# hw4-schematic.net
KiCad netlist of a schematic drawn in EAGLE
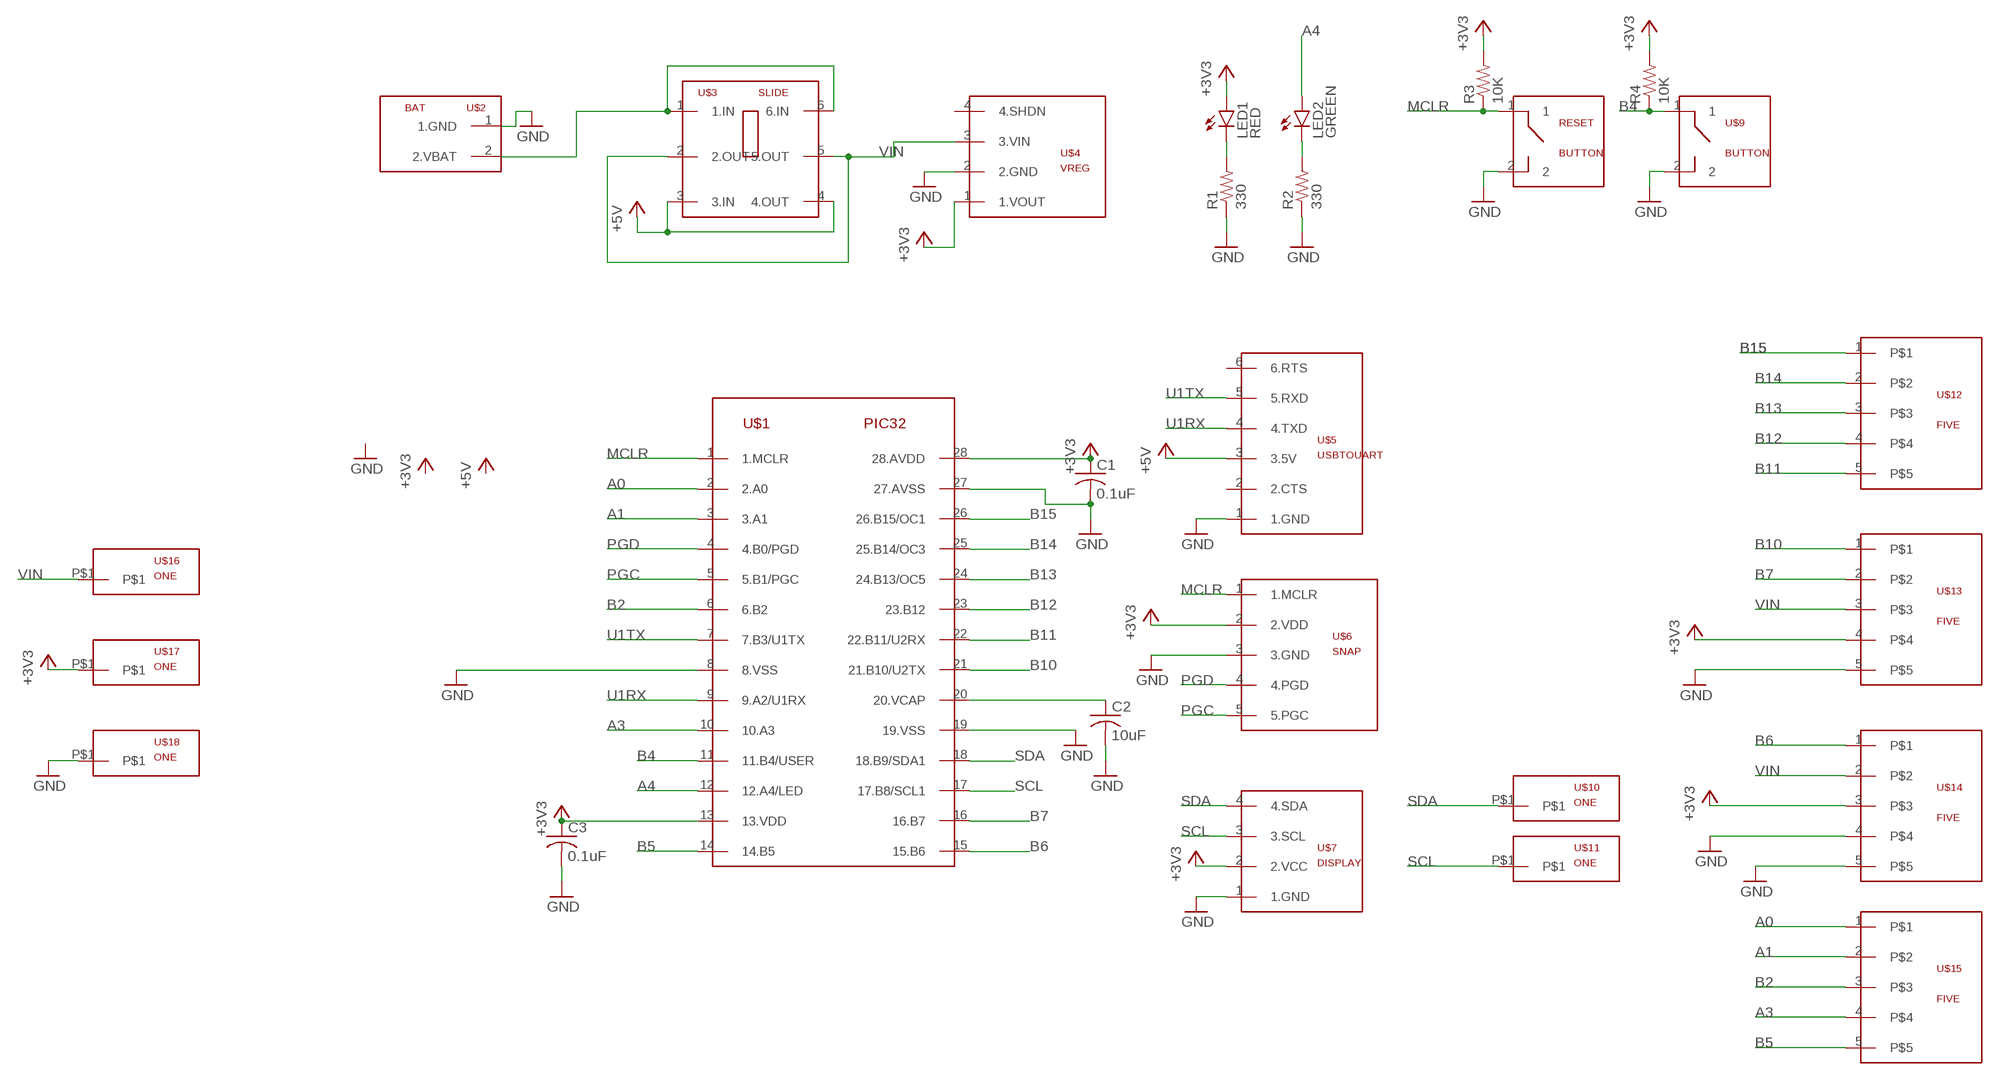
[diagram p0: schematic, sheet 1]

(export (version "E")
  (design (tool "Eeschema 10.0.6"))
  (components
    (comp (ref "C1")
      (value "0.1uF")
      (footprint "eagle-import:C025-024X044")
      (libsource (lib "eagle-import") (part "C-US025-024X044"))
    )
    (comp (ref "C2")
      (value "10uF")
      (footprint "eagle-import:C025-024X044")
      (libsource (lib "eagle-import") (part "C-US025-024X044"))
    )
    (comp (ref "C3")
      (value "0.1uF")
      (footprint "eagle-import:C025-024X044")
      (libsource (lib "eagle-import") (part "C-US025-024X044"))
    )
    (comp (ref "LED1")
      (value "RED")
      (footprint "eagle-import:LED3MM")
      (libsource (lib "eagle-import") (part "LED3MM"))
    )
    (comp (ref "LED2")
      (value "GREEN")
      (footprint "eagle-import:LED3MM")
      (libsource (lib "eagle-import") (part "LED3MM"))
    )
    (comp (ref "R1")
      (value "330")
      (footprint "eagle-import:0207_7")
      (libsource (lib "eagle-import") (part "R-US_0207/7"))
    )
    (comp (ref "R2")
      (value "330")
      (footprint "eagle-import:0207_7")
      (libsource (lib "eagle-import") (part "R-US_0207/7"))
    )
    (comp (ref "R3")
      (value "10K")
      (footprint "eagle-import:0207_7")
      (libsource (lib "eagle-import") (part "R-US_0207/7"))
    )
    (comp (ref "R4")
      (value "10K")
      (footprint "eagle-import:0207_7")
      (libsource (lib "eagle-import") (part "R-US_0207/7"))
    )
    (comp (ref "RESET")
      (value "BUTTON")
      (footprint "eagle-import:BUTTON")
      (libsource (lib "eagle-import") (part "BUTTON"))
    )
    (comp (ref "U$1")
      (value "PIC32")
      (footprint "eagle-import:DIL28-3")
      (libsource (lib "eagle-import") (part "PIC32"))
    )
    (comp (ref "U$2")
      (value "BAT")
      (footprint "eagle-import:BAT")
      (libsource (lib "eagle-import") (part "BAT"))
    )
    (comp (ref "U$3")
      (value "SLIDE")
      (footprint "eagle-import:SLIDE")
      (libsource (lib "eagle-import") (part "SLIDE"))
    )
    (comp (ref "U$4")
      (value "VREG")
      (footprint "eagle-import:VREG")
      (libsource (lib "eagle-import") (part "VREG"))
    )
    (comp (ref "U$5")
      (value "USBTOUART")
      (footprint "eagle-import:USBTOUART")
      (libsource (lib "eagle-import") (part "USBTOUART"))
    )
    (comp (ref "U$6")
      (value "SNAP")
      (footprint "eagle-import:SNAP")
      (libsource (lib "eagle-import") (part "SNAP"))
    )
    (comp (ref "U$7")
      (value "DISPLAY")
      (footprint "eagle-import:DISPLAY")
      (libsource (lib "eagle-import") (part "DISPLAY"))
    )
    (comp (ref "U$9")
      (value "BUTTON")
      (footprint "eagle-import:BUTTON")
      (libsource (lib "eagle-import") (part "BUTTON"))
    )
    (comp (ref "U$10")
      (value "ONE")
      (footprint "eagle-import:ONE")
      (libsource (lib "eagle-import") (part "ONE"))
    )
    (comp (ref "U$11")
      (value "ONE")
      (footprint "eagle-import:ONE")
      (libsource (lib "eagle-import") (part "ONE"))
    )
    (comp (ref "U$12")
      (value "FIVE")
      (footprint "eagle-import:FIVE")
      (libsource (lib "eagle-import") (part "FIVE"))
    )
    (comp (ref "U$13")
      (value "FIVE")
      (footprint "eagle-import:FIVE")
      (libsource (lib "eagle-import") (part "FIVE"))
    )
    (comp (ref "U$14")
      (value "FIVE")
      (footprint "eagle-import:FIVE")
      (libsource (lib "eagle-import") (part "FIVE"))
    )
    (comp (ref "U$15")
      (value "FIVE")
      (footprint "eagle-import:FIVE")
      (libsource (lib "eagle-import") (part "FIVE"))
    )
    (comp (ref "U$16")
      (value "ONE")
      (footprint "eagle-import:ONE")
      (libsource (lib "eagle-import") (part "ONE"))
    )
    (comp (ref "U$17")
      (value "ONE")
      (footprint "eagle-import:ONE")
      (libsource (lib "eagle-import") (part "ONE"))
    )
    (comp (ref "U$18")
      (value "ONE")
      (footprint "eagle-import:ONE")
      (libsource (lib "eagle-import") (part "ONE"))
    )
  )
  (nets
    (net (code "1") (name "+3V3") (class "Default")
      (node (ref "C1") (pin "1") (pinfunction "1_1") (pintype "passive"))
      (node (ref "C3") (pin "1") (pinfunction "1_1") (pintype "passive"))
      (node (ref "LED1") (pin "A") (pinfunction "A_A") (pintype "passive"))
      (node (ref "R3") (pin "2") (pinfunction "2_2") (pintype "passive"))
      (node (ref "R4") (pin "2") (pinfunction "2_2") (pintype "passive"))
      (node (ref "U$1") (pin "13") (pinfunction "13.VDD_13") (pintype "bidirectional"))
      (node (ref "U$1") (pin "28") (pinfunction "28.AVDD_28") (pintype "bidirectional"))
      (node (ref "U$13") (pin "4") (pinfunction "P$4_4") (pintype "bidirectional"))
      (node (ref "U$14") (pin "3") (pinfunction "P$3_3") (pintype "bidirectional"))
      (node (ref "U$17") (pin "P$1") (pinfunction "P$1_P$1") (pintype "bidirectional"))
      (node (ref "U$4") (pin "1") (pinfunction "1.VOUT_1") (pintype "bidirectional"))
      (node (ref "U$6") (pin "2") (pinfunction "2.VDD_2") (pintype "bidirectional"))
      (node (ref "U$7") (pin "2") (pinfunction "2.VCC_2") (pintype "bidirectional"))
    )
    (net (code "2") (name "+5V") (class "Default")
      (node (ref "U$3") (pin "3") (pinfunction "3.IN_3") (pintype "bidirectional"))
      (node (ref "U$3") (pin "4") (pinfunction "4.OUT_4") (pintype "bidirectional"))
      (node (ref "U$5") (pin "3") (pinfunction "3.5V_3") (pintype "bidirectional"))
    )
    (net (code "3") (name "/A0") (class "Default")
      (node (ref "U$1") (pin "2") (pinfunction "2.A0_2") (pintype "bidirectional"))
      (node (ref "U$15") (pin "1") (pinfunction "P$1_1") (pintype "bidirectional"))
    )
    (net (code "4") (name "/A1") (class "Default")
      (node (ref "U$1") (pin "3") (pinfunction "3.A1_3") (pintype "bidirectional"))
      (node (ref "U$15") (pin "2") (pinfunction "P$2_2") (pintype "bidirectional"))
    )
    (net (code "5") (name "/A3") (class "Default")
      (node (ref "U$1") (pin "10") (pinfunction "10.A3_10") (pintype "bidirectional"))
      (node (ref "U$15") (pin "4") (pinfunction "P$4_4") (pintype "bidirectional"))
    )
    (net (code "6") (name "/A4") (class "Default")
      (node (ref "LED2") (pin "A") (pinfunction "A_A") (pintype "passive"))
      (node (ref "U$1") (pin "12") (pinfunction "12.A4/LED_12") (pintype "bidirectional"))
    )
    (net (code "7") (name "/B2") (class "Default")
      (node (ref "U$1") (pin "6") (pinfunction "6.B2_6") (pintype "bidirectional"))
      (node (ref "U$15") (pin "3") (pinfunction "P$3_3") (pintype "bidirectional"))
    )
    (net (code "8") (name "/B4") (class "Default")
      (node (ref "R4") (pin "1") (pinfunction "1_1") (pintype "passive"))
      (node (ref "U$1") (pin "11") (pinfunction "11.B4/USER_11") (pintype "bidirectional"))
      (node (ref "U$9") (pin "1") (pinfunction "1_1") (pintype "bidirectional"))
    )
    (net (code "9") (name "/B5") (class "Default")
      (node (ref "U$1") (pin "14") (pinfunction "14.B5_14") (pintype "bidirectional"))
      (node (ref "U$15") (pin "5") (pinfunction "P$5_5") (pintype "bidirectional"))
    )
    (net (code "10") (name "/B6") (class "Default")
      (node (ref "U$1") (pin "15") (pinfunction "15.B6_15") (pintype "bidirectional"))
      (node (ref "U$14") (pin "1") (pinfunction "P$1_1") (pintype "bidirectional"))
    )
    (net (code "11") (name "/B7") (class "Default")
      (node (ref "U$1") (pin "16") (pinfunction "16.B7_16") (pintype "bidirectional"))
      (node (ref "U$13") (pin "2") (pinfunction "P$2_2") (pintype "bidirectional"))
    )
    (net (code "12") (name "/B10") (class "Default")
      (node (ref "U$1") (pin "21") (pinfunction "21.B10/U2TX_21") (pintype "bidirectional"))
      (node (ref "U$13") (pin "1") (pinfunction "P$1_1") (pintype "bidirectional"))
    )
    (net (code "13") (name "/B11") (class "Default")
      (node (ref "U$1") (pin "22") (pinfunction "22.B11/U2RX_22") (pintype "bidirectional"))
      (node (ref "U$12") (pin "5") (pinfunction "P$5_5") (pintype "bidirectional"))
    )
    (net (code "14") (name "/B12") (class "Default")
      (node (ref "U$1") (pin "23") (pinfunction "23.B12_23") (pintype "bidirectional"))
      (node (ref "U$12") (pin "4") (pinfunction "P$4_4") (pintype "bidirectional"))
    )
    (net (code "15") (name "/B13") (class "Default")
      (node (ref "U$1") (pin "24") (pinfunction "24.B13/OC5_24") (pintype "bidirectional"))
      (node (ref "U$12") (pin "3") (pinfunction "P$3_3") (pintype "bidirectional"))
    )
    (net (code "16") (name "/B14") (class "Default")
      (node (ref "U$1") (pin "25") (pinfunction "25.B14/OC3_25") (pintype "bidirectional"))
      (node (ref "U$12") (pin "2") (pinfunction "P$2_2") (pintype "bidirectional"))
    )
    (net (code "17") (name "/B15") (class "Default")
      (node (ref "U$1") (pin "26") (pinfunction "26.B15/OC1_26") (pintype "bidirectional"))
      (node (ref "U$12") (pin "1") (pinfunction "P$1_1") (pintype "bidirectional"))
    )
    (net (code "18") (name "/MCLR") (class "Default")
      (node (ref "R3") (pin "1") (pinfunction "1_1") (pintype "passive"))
      (node (ref "RESET") (pin "1") (pinfunction "1_1") (pintype "bidirectional"))
      (node (ref "U$1") (pin "1") (pinfunction "1.MCLR_1") (pintype "bidirectional"))
      (node (ref "U$6") (pin "1") (pinfunction "1.MCLR_1") (pintype "bidirectional"))
    )
    (net (code "19") (name "/PGC") (class "Default")
      (node (ref "U$1") (pin "5") (pinfunction "5.B1/PGC_5") (pintype "bidirectional"))
      (node (ref "U$6") (pin "5") (pinfunction "5.PGC_5") (pintype "bidirectional"))
    )
    (net (code "20") (name "/PGD") (class "Default")
      (node (ref "U$1") (pin "4") (pinfunction "4.B0/PGD_4") (pintype "bidirectional"))
      (node (ref "U$6") (pin "4") (pinfunction "4.PGD_4") (pintype "bidirectional"))
    )
    (net (code "21") (name "/SCL") (class "Default")
      (node (ref "U$1") (pin "17") (pinfunction "17.B8/SCL1_17") (pintype "bidirectional"))
      (node (ref "U$11") (pin "P$1") (pinfunction "P$1_P$1") (pintype "bidirectional"))
      (node (ref "U$7") (pin "3") (pinfunction "3.SCL_3") (pintype "bidirectional"))
    )
    (net (code "22") (name "/SDA") (class "Default")
      (node (ref "U$1") (pin "18") (pinfunction "18.B9/SDA1_18") (pintype "bidirectional"))
      (node (ref "U$10") (pin "P$1") (pinfunction "P$1_P$1") (pintype "bidirectional"))
      (node (ref "U$7") (pin "4") (pinfunction "4.SDA_4") (pintype "bidirectional"))
    )
    (net (code "23") (name "/U1RX") (class "Default")
      (node (ref "U$1") (pin "9") (pinfunction "9.A2/U1RX_9") (pintype "bidirectional"))
      (node (ref "U$5") (pin "4") (pinfunction "4.TXD_4") (pintype "bidirectional"))
    )
    (net (code "24") (name "/U1TX") (class "Default")
      (node (ref "U$1") (pin "7") (pinfunction "7.B3/U1TX_7") (pintype "bidirectional"))
      (node (ref "U$5") (pin "5") (pinfunction "5.RXD_5") (pintype "bidirectional"))
    )
    (net (code "25") (name "/VIN") (class "Default")
      (node (ref "U$13") (pin "3") (pinfunction "P$3_3") (pintype "bidirectional"))
      (node (ref "U$14") (pin "2") (pinfunction "P$2_2") (pintype "bidirectional"))
      (node (ref "U$16") (pin "P$1") (pinfunction "P$1_P$1") (pintype "bidirectional"))
      (node (ref "U$3") (pin "2") (pinfunction "2.OUT_2") (pintype "bidirectional"))
      (node (ref "U$3") (pin "5") (pinfunction "5.OUT_5") (pintype "bidirectional"))
      (node (ref "U$4") (pin "3") (pinfunction "3.VIN_3") (pintype "bidirectional"))
    )
    (net (code "26") (name "GND") (class "Default")
      (node (ref "C1") (pin "2") (pinfunction "2_2") (pintype "passive"))
      (node (ref "C2") (pin "2") (pinfunction "2_2") (pintype "passive"))
      (node (ref "C3") (pin "2") (pinfunction "2_2") (pintype "passive"))
      (node (ref "R1") (pin "1") (pinfunction "1_1") (pintype "passive"))
      (node (ref "R2") (pin "1") (pinfunction "1_1") (pintype "passive"))
      (node (ref "RESET") (pin "2") (pinfunction "2_2") (pintype "bidirectional"))
      (node (ref "U$1") (pin "19") (pinfunction "19.VSS_19") (pintype "bidirectional"))
      (node (ref "U$1") (pin "27") (pinfunction "27.AVSS_27") (pintype "bidirectional"))
      (node (ref "U$1") (pin "8") (pinfunction "8.VSS_8") (pintype "bidirectional"))
      (node (ref "U$13") (pin "5") (pinfunction "P$5_5") (pintype "bidirectional"))
      (node (ref "U$14") (pin "4") (pinfunction "P$4_4") (pintype "bidirectional"))
      (node (ref "U$14") (pin "5") (pinfunction "P$5_5") (pintype "bidirectional"))
      (node (ref "U$18") (pin "P$1") (pinfunction "P$1_P$1") (pintype "bidirectional"))
      (node (ref "U$2") (pin "1") (pinfunction "1.GND_1") (pintype "bidirectional"))
      (node (ref "U$4") (pin "2") (pinfunction "2.GND_2") (pintype "bidirectional"))
      (node (ref "U$5") (pin "1") (pinfunction "1.GND_1") (pintype "bidirectional"))
      (node (ref "U$6") (pin "3") (pinfunction "3.GND_3") (pintype "bidirectional"))
      (node (ref "U$7") (pin "1") (pinfunction "1.GND_1") (pintype "bidirectional"))
      (node (ref "U$9") (pin "2") (pinfunction "2_2") (pintype "bidirectional"))
    )
    (net (code "27") (name "Net-(LED1-C)") (class "Default")
      (node (ref "LED1") (pin "K") (pinfunction "C_K") (pintype "passive"))
      (node (ref "R1") (pin "2") (pinfunction "2_2") (pintype "passive"))
    )
    (net (code "28") (name "Net-(LED2-C)") (class "Default")
      (node (ref "LED2") (pin "K") (pinfunction "C_K") (pintype "passive"))
      (node (ref "R2") (pin "2") (pinfunction "2_2") (pintype "passive"))
    )
    (net (code "29") (name "Net-(U$1-20.VCAP)") (class "Default")
      (node (ref "C2") (pin "1") (pinfunction "1_1") (pintype "passive"))
      (node (ref "U$1") (pin "20") (pinfunction "20.VCAP_20") (pintype "bidirectional"))
    )
    (net (code "30") (name "Net-(U$2-2.VBAT)") (class "Default")
      (node (ref "U$2") (pin "2") (pinfunction "2.VBAT_2") (pintype "bidirectional"))
      (node (ref "U$3") (pin "1") (pinfunction "1.IN_1") (pintype "bidirectional"))
      (node (ref "U$3") (pin "6") (pinfunction "6.IN_6") (pintype "bidirectional"))
    )
    (net (code "31") (name "unconnected-(U$4-4.SHDN-Pad4)") (class "Default")
      (node (ref "U$4") (pin "4") (pinfunction "4.SHDN_4") (pintype "bidirectional"))
    )
    (net (code "32") (name "unconnected-(U$5-2.CTS-Pad2)") (class "Default")
      (node (ref "U$5") (pin "2") (pinfunction "2.CTS_2") (pintype "bidirectional"))
    )
    (net (code "33") (name "unconnected-(U$5-6.RTS-Pad6)") (class "Default")
      (node (ref "U$5") (pin "6") (pinfunction "6.RTS_6") (pintype "bidirectional"))
    )
  )
)
